# BOBBYPIN.net
KiCad netlist of a schematic drawn in EAGLE
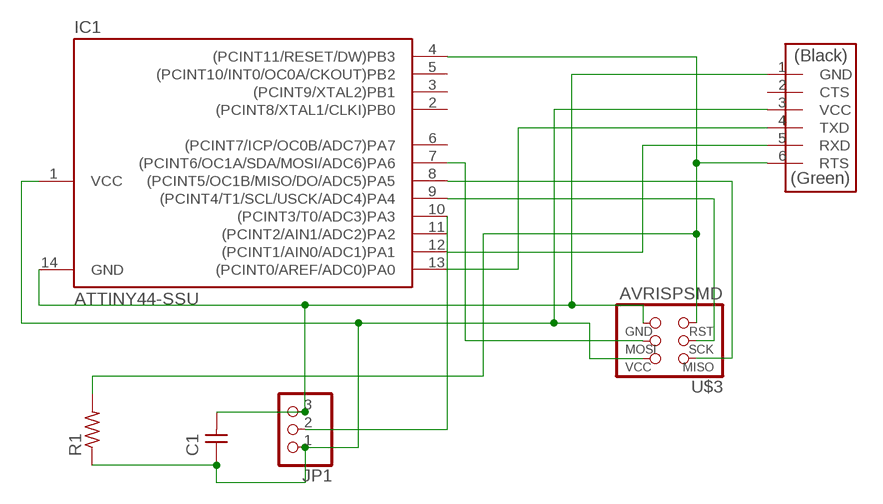
[diagram p0: schematic, sheet 1]

(export (version "E")
  (design (tool "Eeschema 10.0.6"))
  (components
    (comp (ref "C1")
      (value "CAP-UNPOLARIZEDFAB")
      (footprint "eagle-import:C1206FAB")
      (libsource (lib "eagle-import") (part "CAP-UNPOLARIZEDFAB"))
    )
    (comp (ref "IC1")
      (value "ATTINY44-SSU")
      (footprint "eagle-import:SOIC14")
      (libsource (lib "eagle-import") (part "ATTINY44-SSU"))
    )
    (comp (ref "JP1")
      (value "PINHD-1X3/90")
      (footprint "eagle-import:1X03_90")
      (libsource (lib "eagle-import") (part "PINHD-1X3/90"))
    )
    (comp (ref "R1")
      (value "RES-US1206FAB")
      (footprint "eagle-import:R1206FAB")
      (libsource (lib "eagle-import") (part "RES-US1206FAB"))
    )
    (comp (ref "U$2")
      (value "FTDI-SMD-HEADER")
      (footprint "eagle-import:1X06SMD")
      (libsource (lib "eagle-import") (part "FTDI-SMD-HEADER"))
    )
    (comp (ref "U$3")
      (value "AVRISPSMD")
      (footprint "eagle-import:2X03SMD")
      (libsource (lib "eagle-import") (part "AVRISPSMD"))
    )
  )
  (nets
    (net (code "1") (name "Net-(IC1-(PCINT0{slash}AREF{slash}ADC0)PA0)") (class "Default")
      (node (ref "IC1") (pin "13") (pinfunction "(PCINT0/AREF/ADC0)PA0_13") (pintype "bidirectional"))
      (node (ref "U$2") (pin "4") (pinfunction "TXD_4") (pintype "bidirectional"))
    )
    (net (code "2") (name "Net-(IC1-(PCINT1{slash}AIN0{slash}ADC1)PA1)") (class "Default")
      (node (ref "IC1") (pin "12") (pinfunction "(PCINT1/AIN0/ADC1)PA1_12") (pintype "bidirectional"))
      (node (ref "U$2") (pin "5") (pinfunction "RXD_5") (pintype "bidirectional"))
    )
    (net (code "3") (name "Net-(IC1-(PCINT3{slash}T0{slash}ADC3)PA3)") (class "Default")
      (node (ref "IC1") (pin "10") (pinfunction "(PCINT3/T0/ADC3)PA3_10") (pintype "bidirectional"))
      (node (ref "JP1") (pin "2") (pinfunction "2_2") (pintype "passive"))
    )
    (net (code "4") (name "Net-(IC1-(PCINT4{slash}T1{slash}SCL{slash}USCK{slash}ADC4)PA4)") (class "Default")
      (node (ref "IC1") (pin "9") (pinfunction "(PCINT4/T1/SCL/USCK/ADC4)PA4_9") (pintype "bidirectional"))
      (node (ref "U$3") (pin "3") (pinfunction "SCK_3") (pintype "passive"))
    )
    (net (code "5") (name "Net-(IC1-(PCINT5{slash}OC1B{slash}MISO{slash}DO{slash}ADC5)PA5)") (class "Default")
      (node (ref "IC1") (pin "8") (pinfunction "(PCINT5/OC1B/MISO/DO/ADC5)PA5_8") (pintype "bidirectional"))
      (node (ref "U$3") (pin "1") (pinfunction "MISO_1") (pintype "passive"))
    )
    (net (code "6") (name "Net-(IC1-(PCINT6{slash}OC1A{slash}SDA{slash}MOSI{slash}ADC6)PA6)") (class "Default")
      (node (ref "IC1") (pin "7") (pinfunction "(PCINT6/OC1A/SDA/MOSI/ADC6)PA6_7") (pintype "bidirectional"))
      (node (ref "U$3") (pin "4") (pinfunction "MOSI_4") (pintype "passive"))
    )
    (net (code "7") (name "Net-(IC1-(PCINT11{slash}RESET{slash}DW)PB3)") (class "Default")
      (node (ref "IC1") (pin "4") (pinfunction "(PCINT11/RESET/DW)PB3_4") (pintype "bidirectional"))
      (node (ref "R1") (pin "2") (pinfunction "2_2") (pintype "passive"))
      (node (ref "U$2") (pin "6") (pinfunction "RTS_6") (pintype "bidirectional"))
      (node (ref "U$3") (pin "5") (pinfunction "RST_5") (pintype "passive"))
    )
    (net (code "8") (name "Net-(IC1-GND)") (class "Default")
      (node (ref "C1") (pin "2") (pinfunction "2_2") (pintype "passive"))
      (node (ref "IC1") (pin "14") (pinfunction "GND_14") (pintype "power_in"))
      (node (ref "JP1") (pin "3") (pinfunction "3_3") (pintype "passive"))
      (node (ref "U$2") (pin "1") (pinfunction "GND_1") (pintype "bidirectional"))
      (node (ref "U$3") (pin "6") (pinfunction "GND_6") (pintype "passive"))
    )
    (net (code "9") (name "Net-(IC1-VCC)") (class "Default")
      (node (ref "C1") (pin "1") (pinfunction "1_1") (pintype "passive"))
      (node (ref "IC1") (pin "1") (pinfunction "VCC_1") (pintype "power_in"))
      (node (ref "JP1") (pin "1") (pinfunction "1_1") (pintype "passive"))
      (node (ref "R1") (pin "1") (pinfunction "1_1") (pintype "passive"))
      (node (ref "U$2") (pin "3") (pinfunction "VCC_3") (pintype "bidirectional"))
      (node (ref "U$3") (pin "2") (pinfunction "VCC_2") (pintype "passive"))
    )
    (net (code "10") (name "unconnected-(IC1-(PCINT2{slash}AIN1{slash}ADC2)PA2-Pad11)") (class "Default")
      (node (ref "IC1") (pin "11") (pinfunction "(PCINT2/AIN1/ADC2)PA2_11") (pintype "bidirectional"))
    )
    (net (code "11") (name "unconnected-(IC1-(PCINT7{slash}ICP{slash}OC0B{slash}ADC7)PA7-Pad6)") (class "Default")
      (node (ref "IC1") (pin "6") (pinfunction "(PCINT7/ICP/OC0B/ADC7)PA7_6") (pintype "bidirectional"))
    )
    (net (code "12") (name "unconnected-(IC1-(PCINT8{slash}XTAL1{slash}CLKI)PB0-Pad2)") (class "Default")
      (node (ref "IC1") (pin "2") (pinfunction "(PCINT8/XTAL1/CLKI)PB0_2") (pintype "bidirectional"))
    )
    (net (code "13") (name "unconnected-(IC1-(PCINT9{slash}XTAL2)PB1-Pad3)") (class "Default")
      (node (ref "IC1") (pin "3") (pinfunction "(PCINT9/XTAL2)PB1_3") (pintype "bidirectional"))
    )
    (net (code "14") (name "unconnected-(IC1-(PCINT10{slash}INT0{slash}OC0A{slash}CKOUT)PB2-Pad5)") (class "Default")
      (node (ref "IC1") (pin "5") (pinfunction "(PCINT10/INT0/OC0A/CKOUT)PB2_5") (pintype "bidirectional"))
    )
    (net (code "15") (name "unconnected-(U$2-CTS-Pad2)") (class "Default")
      (node (ref "U$2") (pin "2") (pinfunction "CTS_2") (pintype "bidirectional"))
    )
  )
)
